# Powersupply.net
KiCad netlist of a schematic drawn in Altium Designer
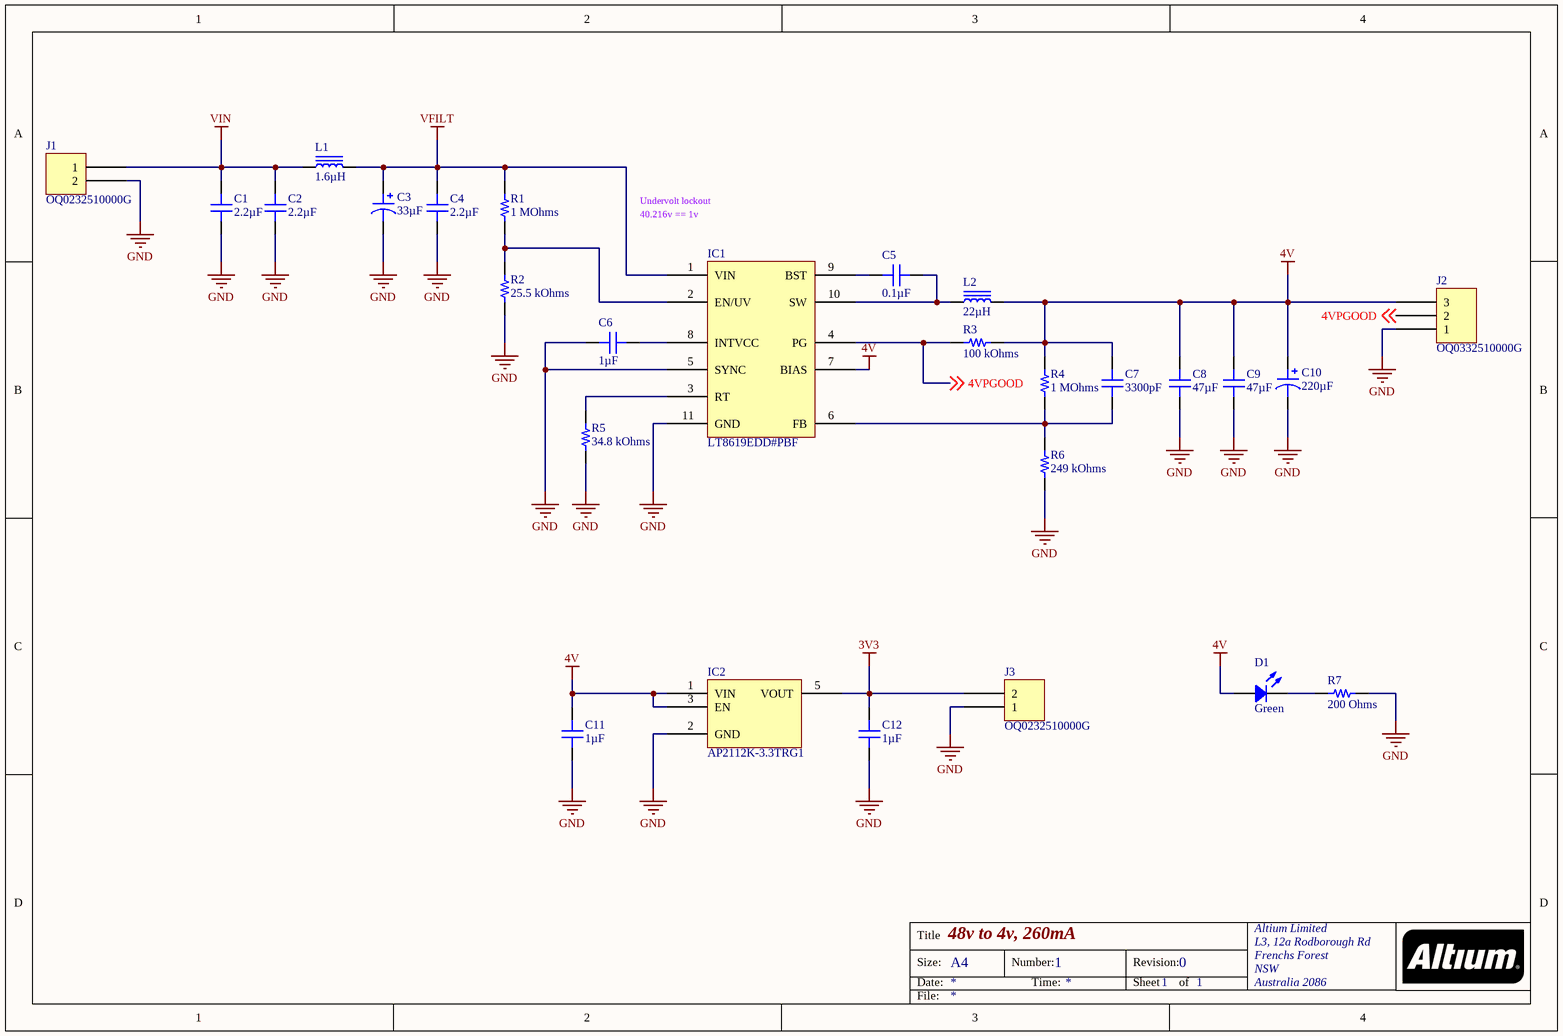
[diagram p0: Powersupply.SchDoc]

(export (version "E")
  (design (tool "Eeschema 10.0.6"))
  (components
    (comp (ref "C1")
      (value "2.2µF")
      (footprint "CAP 1206_3216 - 1.8MM")
      (description "CAP CER 2.2UF 100V X7R 1206")
      (fields (field (name "PART NUMBER") "12061C225KAT2A") (field (name "MANUFACTURER") "AVX Corporation"))
      (libsource (lib "Celestial Altium Library - altium_library") (part "Capacitor"))
    )
    (comp (ref "C2")
      (value "2.2µF")
      (footprint "CAP 1206_3216 - 1.8MM")
      (description "CAP CER 2.2UF 100V X7R 1206")
      (fields (field (name "PART NUMBER") "12061C225KAT2A") (field (name "MANUFACTURER") "AVX Corporation"))
      (libsource (lib "Celestial Altium Library - altium_library") (part "Capacitor"))
    )
    (comp (ref "C3")
      (value "33µF")
      (footprint "CAP ALSMD 8.3MM H10.5MM")
      (description "CAP ALUM POLY HYB 33UF 63V SMD")
      (fields
        (field (name "PART NUMBER") "EEH-ZA1J330P")
        (field (name "MANUFACTURER") "Panasonic Electronic Components")
      )
      (libsource (lib "Celestial Altium Library - altium_library") (part "Polarised Capacitor"))
    )
    (comp (ref "C4")
      (value "2.2µF")
      (footprint "CAP 1206_3216 - 1.8MM")
      (description "CAP CER 2.2UF 100V X7R 1206")
      (fields (field (name "PART NUMBER") "12061C225KAT2A") (field (name "MANUFACTURER") "AVX Corporation"))
      (libsource (lib "Celestial Altium Library - altium_library") (part "Capacitor"))
    )
    (comp (ref "C5")
      (value "0.1µF")
      (footprint "CAP 0603_1608")
      (description "CAP CER 0.1UF 100V X7R 0603")
      (fields (field (name "PART NUMBER") "HMK107B7104MA-T") (field (name "MANUFACTURER") "Taiyo Yuden"))
      (libsource (lib "Celestial Altium Library - altium_library") (part "Capacitor"))
    )
    (comp (ref "C6")
      (value "1µF")
      (footprint "CAP 0402_1005")
      (description "CAP CER 1UF 10V X6S 0402")
      (fields (field (name "PART NUMBER") "LMK105C6105MV-F") (field (name "MANUFACTURER") "Taiyo Yuden"))
      (libsource (lib "Celestial Altium Library - altium_library") (part "Capacitor"))
    )
    (comp (ref "C7")
      (value "3300pF")
      (footprint "CAP 0402_1005")
      (description "CAP CER 3300PF 50V X7R 0402")
      (fields (field (name "PART NUMBER") "CC0402KRX7R9BB332") (field (name "MANUFACTURER") "Yageo"))
      (libsource (lib "Celestial Altium Library - altium_library") (part "Capacitor"))
    )
    (comp (ref "C8")
      (value "47µF")
      (footprint "CAP 1206_3216 - 1.8MM")
      (description "CAP CER 47UF 10V X5R 1206")
      (fields (field (name "PART NUMBER") "LMK316BJ476ML-T") (field (name "MANUFACTURER") "Taiyo Yuden"))
      (libsource (lib "Celestial Altium Library - altium_library") (part "Capacitor"))
    )
    (comp (ref "C9")
      (value "47µF")
      (footprint "CAP 1206_3216 - 1.8MM")
      (description "CAP CER 47UF 10V X5R 1206")
      (fields (field (name "PART NUMBER") "LMK316BJ476ML-T") (field (name "MANUFACTURER") "Taiyo Yuden"))
      (libsource (lib "Celestial Altium Library - altium_library") (part "Capacitor"))
    )
    (comp (ref "C10")
      (value "220µF")
      (footprint "CAP ALSMD POLY 8.3MM H6.7MM")
      (description "CAP ALUM POLY 220UF 20% 6.3V SMD")
      (fields
        (field (name "PART NUMBER") "APXA6R3ARA221MH70G")
        (field (name "MANUFACTURER") "United Chemi-Con")
      )
      (libsource (lib "Celestial Altium Library - altium_library") (part "Polarised Capacitor"))
    )
    (comp (ref "C11")
      (value "1µF")
      (footprint "CAP 0402_1005")
      (description "CAP CER 1UF 10V X6S 0402")
      (fields (field (name "PART NUMBER") "LMK105C6105MV-F") (field (name "MANUFACTURER") "Taiyo Yuden"))
      (libsource (lib "Celestial Altium Library - altium_library") (part "Capacitor"))
    )
    (comp (ref "C12")
      (value "1µF")
      (footprint "CAP 0402_1005")
      (description "CAP CER 1UF 10V X6S 0402")
      (fields (field (name "PART NUMBER") "LMK105C6105MV-F") (field (name "MANUFACTURER") "Taiyo Yuden"))
      (libsource (lib "Celestial Altium Library - altium_library") (part "Capacitor"))
    )
    (comp (ref "D1")
      (value "Green")
      (footprint "LED 0603_1608 GREEN")
      (description "LED GREEN CLEAR SMD")
      (fields (field (name "PART NUMBER") "LTST-C191KGKT") (field (name "MANUFACTURER") "Lite-On Inc."))
      (libsource (lib "Celestial Altium Library - altium_library") (part "LED"))
    )
    (comp (ref "IC1")
      (value "LT8619EDD#PBF")
      (footprint "ANALOG DFN-10 3x3MM DD")
      (description "IC REG BUCK 0.8V 1.2A 10DFN")
      (fields (field (name "MANUFACTURER") "Linear Technology/Analog Devices"))
      (libsource (lib "Celestial Altium Library - altium_library") (part "ANALOG LT8619 DD"))
    )
    (comp (ref "IC2")
      (value "AP2112K-3.3TRG1")
      (footprint "DIODES SOT-23-5 W5")
      (description "IC REG LINEAR 3.3V 600MA SOT25")
      (fields (field (name "MANUFACTURER") "Diodes Incorporated"))
      (libsource (lib "Celestial Altium Library - altium_library") (part "DIODES INC AP2112K"))
    )
    (comp (ref "J1")
      (value "OQ0232510000G")
      (footprint "FCI 06-381-2PIN")
      (description "TERM BLOCK HDR 2POS 90DEG 3.81MM")
      (fields (field (name "MANUFACTURER") "Amphenol Anytek"))
      (libsource (lib "Celestial Altium Library - altium_library") (part "2 Pin"))
    )
    (comp (ref "J2")
      (value "OQ0332510000G")
      (footprint "FCI 06-381-3PIN")
      (description "TERM BLOCK HDR 3POS 90DEG 3.81MM")
      (fields (field (name "MANUFACTURER") "Amphenol Anytek"))
      (libsource (lib "Celestial Altium Library - altium_library") (part "3 Pin"))
    )
    (comp (ref "J3")
      (value "OQ0232510000G")
      (footprint "FCI 06-381-2PIN")
      (description "TERM BLOCK HDR 2POS 90DEG 3.81MM")
      (fields (field (name "MANUFACTURER") "Amphenol Anytek"))
      (libsource (lib "") (part "2 Pin_1"))
    )
    (comp (ref "L1")
      (value "1.6µH")
      (footprint "TDK VLCF4024-2")
      (description "FIXED IND 1.6UH 2.1A 39 MOHM SMD")
      (fields
        (field (name "PART NUMBER") "VLCF4024T-1R6N2R1-2")
        (field (name "MANUFACTURER") "TDK Corporation")
      )
      (libsource (lib "Celestial Altium Library - altium_library") (part "Inductor"))
    )
    (comp (ref "L2")
      (value "22µH")
      (footprint "TDK SLF12555")
      (description "FIXED IND 22UH 2.3A 33.8 MOHM")
      (fields
        (field (name "PART NUMBER") "SLF12555T-220M2R3-PF")
        (field (name "MANUFACTURER") "TDK Corporation")
      )
      (libsource (lib "Celestial Altium Library - altium_library") (part "Inductor"))
    )
    (comp (ref "R1")
      (value "1 MOhms")
      (footprint "RES 0402_1005")
      (description "RES SMD 1M OHM 1% 1/10W 0402")
      (fields
        (field (name "PART NUMBER") "ERJ-2RKF1004X")
        (field (name "MANUFACTURER") "Panasonic Electronic Components")
      )
      (libsource (lib "Celestial Altium Library - altium_library") (part "Resistor"))
    )
    (comp (ref "R2")
      (value "25.5 kOhms")
      (footprint "RES 0402_1005")
      (description "RES SMD 25.5K OHM 1% 1/10W 0402")
      (fields
        (field (name "PART NUMBER") "ERJ-2RKF2552X")
        (field (name "MANUFACTURER") "Panasonic Electronic Components")
      )
      (libsource (lib "Celestial Altium Library - altium_library") (part "Resistor"))
    )
    (comp (ref "R3")
      (value "100 kOhms")
      (footprint "RES 0402_1005")
      (description "RES SMD 100K OHM 1% 1/16W 0402")
      (fields
        (field (name "PART NUMBER") "CRG0402F100K")
        (field (name "MANUFACTURER") "TE Connectivity Passive Product")
      )
      (libsource (lib "Celestial Altium Library - altium_library") (part "Resistor"))
    )
    (comp (ref "R4")
      (value "1 MOhms")
      (footprint "RES 0402_1005")
      (description "RES SMD 1M OHM 1% 1/10W 0402")
      (fields
        (field (name "PART NUMBER") "ERJ-2RKF1004X")
        (field (name "MANUFACTURER") "Panasonic Electronic Components")
      )
      (libsource (lib "Celestial Altium Library - altium_library") (part "Resistor"))
    )
    (comp (ref "R5")
      (value "34.8 kOhms")
      (footprint "RES 0402_1005")
      (description "RES SMD 34.8K OHM 1% 1/10W 0402")
      (fields
        (field (name "PART NUMBER") "ERJ-2RKF3482X")
        (field (name "MANUFACTURER") "Panasonic Electronic Components")
      )
      (libsource (lib "Celestial Altium Library - altium_library") (part "Resistor"))
    )
    (comp (ref "R6")
      (value "249 kOhms")
      (footprint "RES 0402_1005")
      (description "RES SMD 249K OHM 1% 1/10W 0402")
      (fields
        (field (name "PART NUMBER") "ERJ-2RKF2493X")
        (field (name "MANUFACTURER") "Panasonic Electronic Components")
      )
      (libsource (lib "Celestial Altium Library - altium_library") (part "Resistor"))
    )
    (comp (ref "R7")
      (value "200 Ohms")
      (footprint "RES 0603_1608")
      (description "RES SMD 200 OHM 5% 1/10W 0603")
      (fields
        (field (name "PART NUMBER") "ERJ-3GEYJ201V")
        (field (name "MANUFACTURER") "Panasonic Electronic Components")
      )
      (libsource (lib "Celestial Altium Library - altium_library") (part "Resistor"))
    )
  )
  (nets
    (net (code "1") (name "3V3") (class "Default")
      (node (ref "C12") (pin "1") (pinfunction "1_1") (pintype "passive"))
      (node (ref "IC2") (pin "5") (pinfunction "VOUT_5") (pintype "passive"))
      (node (ref "J3") (pin "2") (pinfunction "2_2") (pintype "passive"))
    )
    (net (code "2") (name "4V") (class "Default")
      (node (ref "C10") (pin "1") (pinfunction "1_1") (pintype "passive"))
      (node (ref "C11") (pin "1") (pinfunction "1_1") (pintype "passive"))
      (node (ref "C7") (pin "2") (pinfunction "2_2") (pintype "passive"))
      (node (ref "C8") (pin "2") (pinfunction "2_2") (pintype "passive"))
      (node (ref "C9") (pin "2") (pinfunction "2_2") (pintype "passive"))
      (node (ref "D1") (pin "1") (pinfunction "1_1") (pintype "passive"))
      (node (ref "IC1") (pin "7") (pinfunction "BIAS_7") (pintype "passive"))
      (node (ref "IC2") (pin "1") (pinfunction "VIN_1") (pintype "passive"))
      (node (ref "IC2") (pin "3") (pinfunction "EN_3") (pintype "passive"))
      (node (ref "J2") (pin "3") (pinfunction "3_3") (pintype "passive"))
      (node (ref "L2") (pin "2") (pinfunction "2_2") (pintype "passive"))
      (node (ref "R3") (pin "2") (pinfunction "2_2") (pintype "passive"))
      (node (ref "R4") (pin "2") (pinfunction "2_2") (pintype "passive"))
    )
    (net (code "3") (name "4VPGOOD") (class "Default")
      (node (ref "IC1") (pin "4") (pinfunction "PG_4") (pintype "passive"))
      (node (ref "J2") (pin "2") (pinfunction "2_2") (pintype "passive"))
      (node (ref "R3") (pin "1") (pinfunction "1_1") (pintype "passive"))
    )
    (net (code "4") (name "GND") (class "Default")
      (node (ref "C1") (pin "1") (pinfunction "1_1") (pintype "passive"))
      (node (ref "C10") (pin "2") (pinfunction "2_2") (pintype "passive"))
      (node (ref "C11") (pin "2") (pinfunction "2_2") (pintype "passive"))
      (node (ref "C12") (pin "2") (pinfunction "2_2") (pintype "passive"))
      (node (ref "C2") (pin "1") (pinfunction "1_1") (pintype "passive"))
      (node (ref "C3") (pin "2") (pinfunction "2_2") (pintype "passive"))
      (node (ref "C4") (pin "1") (pinfunction "1_1") (pintype "passive"))
      (node (ref "C6") (pin "2") (pinfunction "2_2") (pintype "passive"))
      (node (ref "C8") (pin "1") (pinfunction "1_1") (pintype "passive"))
      (node (ref "C9") (pin "1") (pinfunction "1_1") (pintype "passive"))
      (node (ref "IC1") (pin "11") (pinfunction "GND_11") (pintype "passive"))
      (node (ref "IC1") (pin "5") (pinfunction "SYNC_5") (pintype "passive"))
      (node (ref "IC2") (pin "2") (pinfunction "GND_2") (pintype "passive"))
      (node (ref "J1") (pin "2") (pinfunction "2_2") (pintype "passive"))
      (node (ref "J2") (pin "1") (pinfunction "1_1") (pintype "passive"))
      (node (ref "J3") (pin "1") (pinfunction "1_1") (pintype "passive"))
      (node (ref "R2") (pin "1") (pinfunction "1_1") (pintype "passive"))
      (node (ref "R5") (pin "1") (pinfunction "1_1") (pintype "passive"))
      (node (ref "R6") (pin "1") (pinfunction "1_1") (pintype "passive"))
      (node (ref "R7") (pin "2") (pinfunction "2_2") (pintype "passive"))
    )
    (net (code "5") (name "Net-(D1-Pad2)") (class "Default")
      (node (ref "D1") (pin "2") (pinfunction "2_2") (pintype "passive"))
      (node (ref "R7") (pin "1") (pinfunction "1_1") (pintype "passive"))
    )
    (net (code "6") (name "Net-(IC1-BST)") (class "Default")
      (node (ref "C5") (pin "1") (pinfunction "1_1") (pintype "passive"))
      (node (ref "IC1") (pin "9") (pinfunction "BST_9") (pintype "passive"))
    )
    (net (code "7") (name "Net-(IC1-EN{slash}UV)") (class "Default")
      (node (ref "IC1") (pin "2") (pinfunction "EN/UV_2") (pintype "passive"))
      (node (ref "R1") (pin "1") (pinfunction "1_1") (pintype "passive"))
      (node (ref "R2") (pin "2") (pinfunction "2_2") (pintype "passive"))
    )
    (net (code "8") (name "Net-(IC1-FB)") (class "Default")
      (node (ref "C7") (pin "1") (pinfunction "1_1") (pintype "passive"))
      (node (ref "IC1") (pin "6") (pinfunction "FB_6") (pintype "passive"))
      (node (ref "R4") (pin "1") (pinfunction "1_1") (pintype "passive"))
      (node (ref "R6") (pin "2") (pinfunction "2_2") (pintype "passive"))
    )
    (net (code "9") (name "Net-(IC1-INTVCC)") (class "Default")
      (node (ref "C6") (pin "1") (pinfunction "1_1") (pintype "passive"))
      (node (ref "IC1") (pin "8") (pinfunction "INTVCC_8") (pintype "passive"))
    )
    (net (code "10") (name "Net-(IC1-RT)") (class "Default")
      (node (ref "IC1") (pin "3") (pinfunction "RT_3") (pintype "passive"))
      (node (ref "R5") (pin "2") (pinfunction "2_2") (pintype "passive"))
    )
    (net (code "11") (name "Net-(IC1-SW)") (class "Default")
      (node (ref "C5") (pin "2") (pinfunction "2_2") (pintype "passive"))
      (node (ref "IC1") (pin "10") (pinfunction "SW_10") (pintype "passive"))
      (node (ref "L2") (pin "1") (pinfunction "1_1") (pintype "passive"))
    )
    (net (code "12") (name "VFILT") (class "Default")
      (node (ref "C3") (pin "1") (pinfunction "1_1") (pintype "passive"))
      (node (ref "C4") (pin "2") (pinfunction "2_2") (pintype "passive"))
      (node (ref "IC1") (pin "1") (pinfunction "VIN_1") (pintype "passive"))
      (node (ref "L1") (pin "2") (pinfunction "2_2") (pintype "passive"))
      (node (ref "R1") (pin "2") (pinfunction "2_2") (pintype "passive"))
    )
    (net (code "13") (name "VIN") (class "Default")
      (node (ref "C1") (pin "2") (pinfunction "2_2") (pintype "passive"))
      (node (ref "C2") (pin "2") (pinfunction "2_2") (pintype "passive"))
      (node (ref "J1") (pin "1") (pinfunction "1_1") (pintype "passive"))
      (node (ref "L1") (pin "1") (pinfunction "1_1") (pintype "passive"))
    )
  )
)
